# ProDocument__DCDC_2024-01-08.net
KiCad netlist of a schematic drawn in EasyEDA Pro
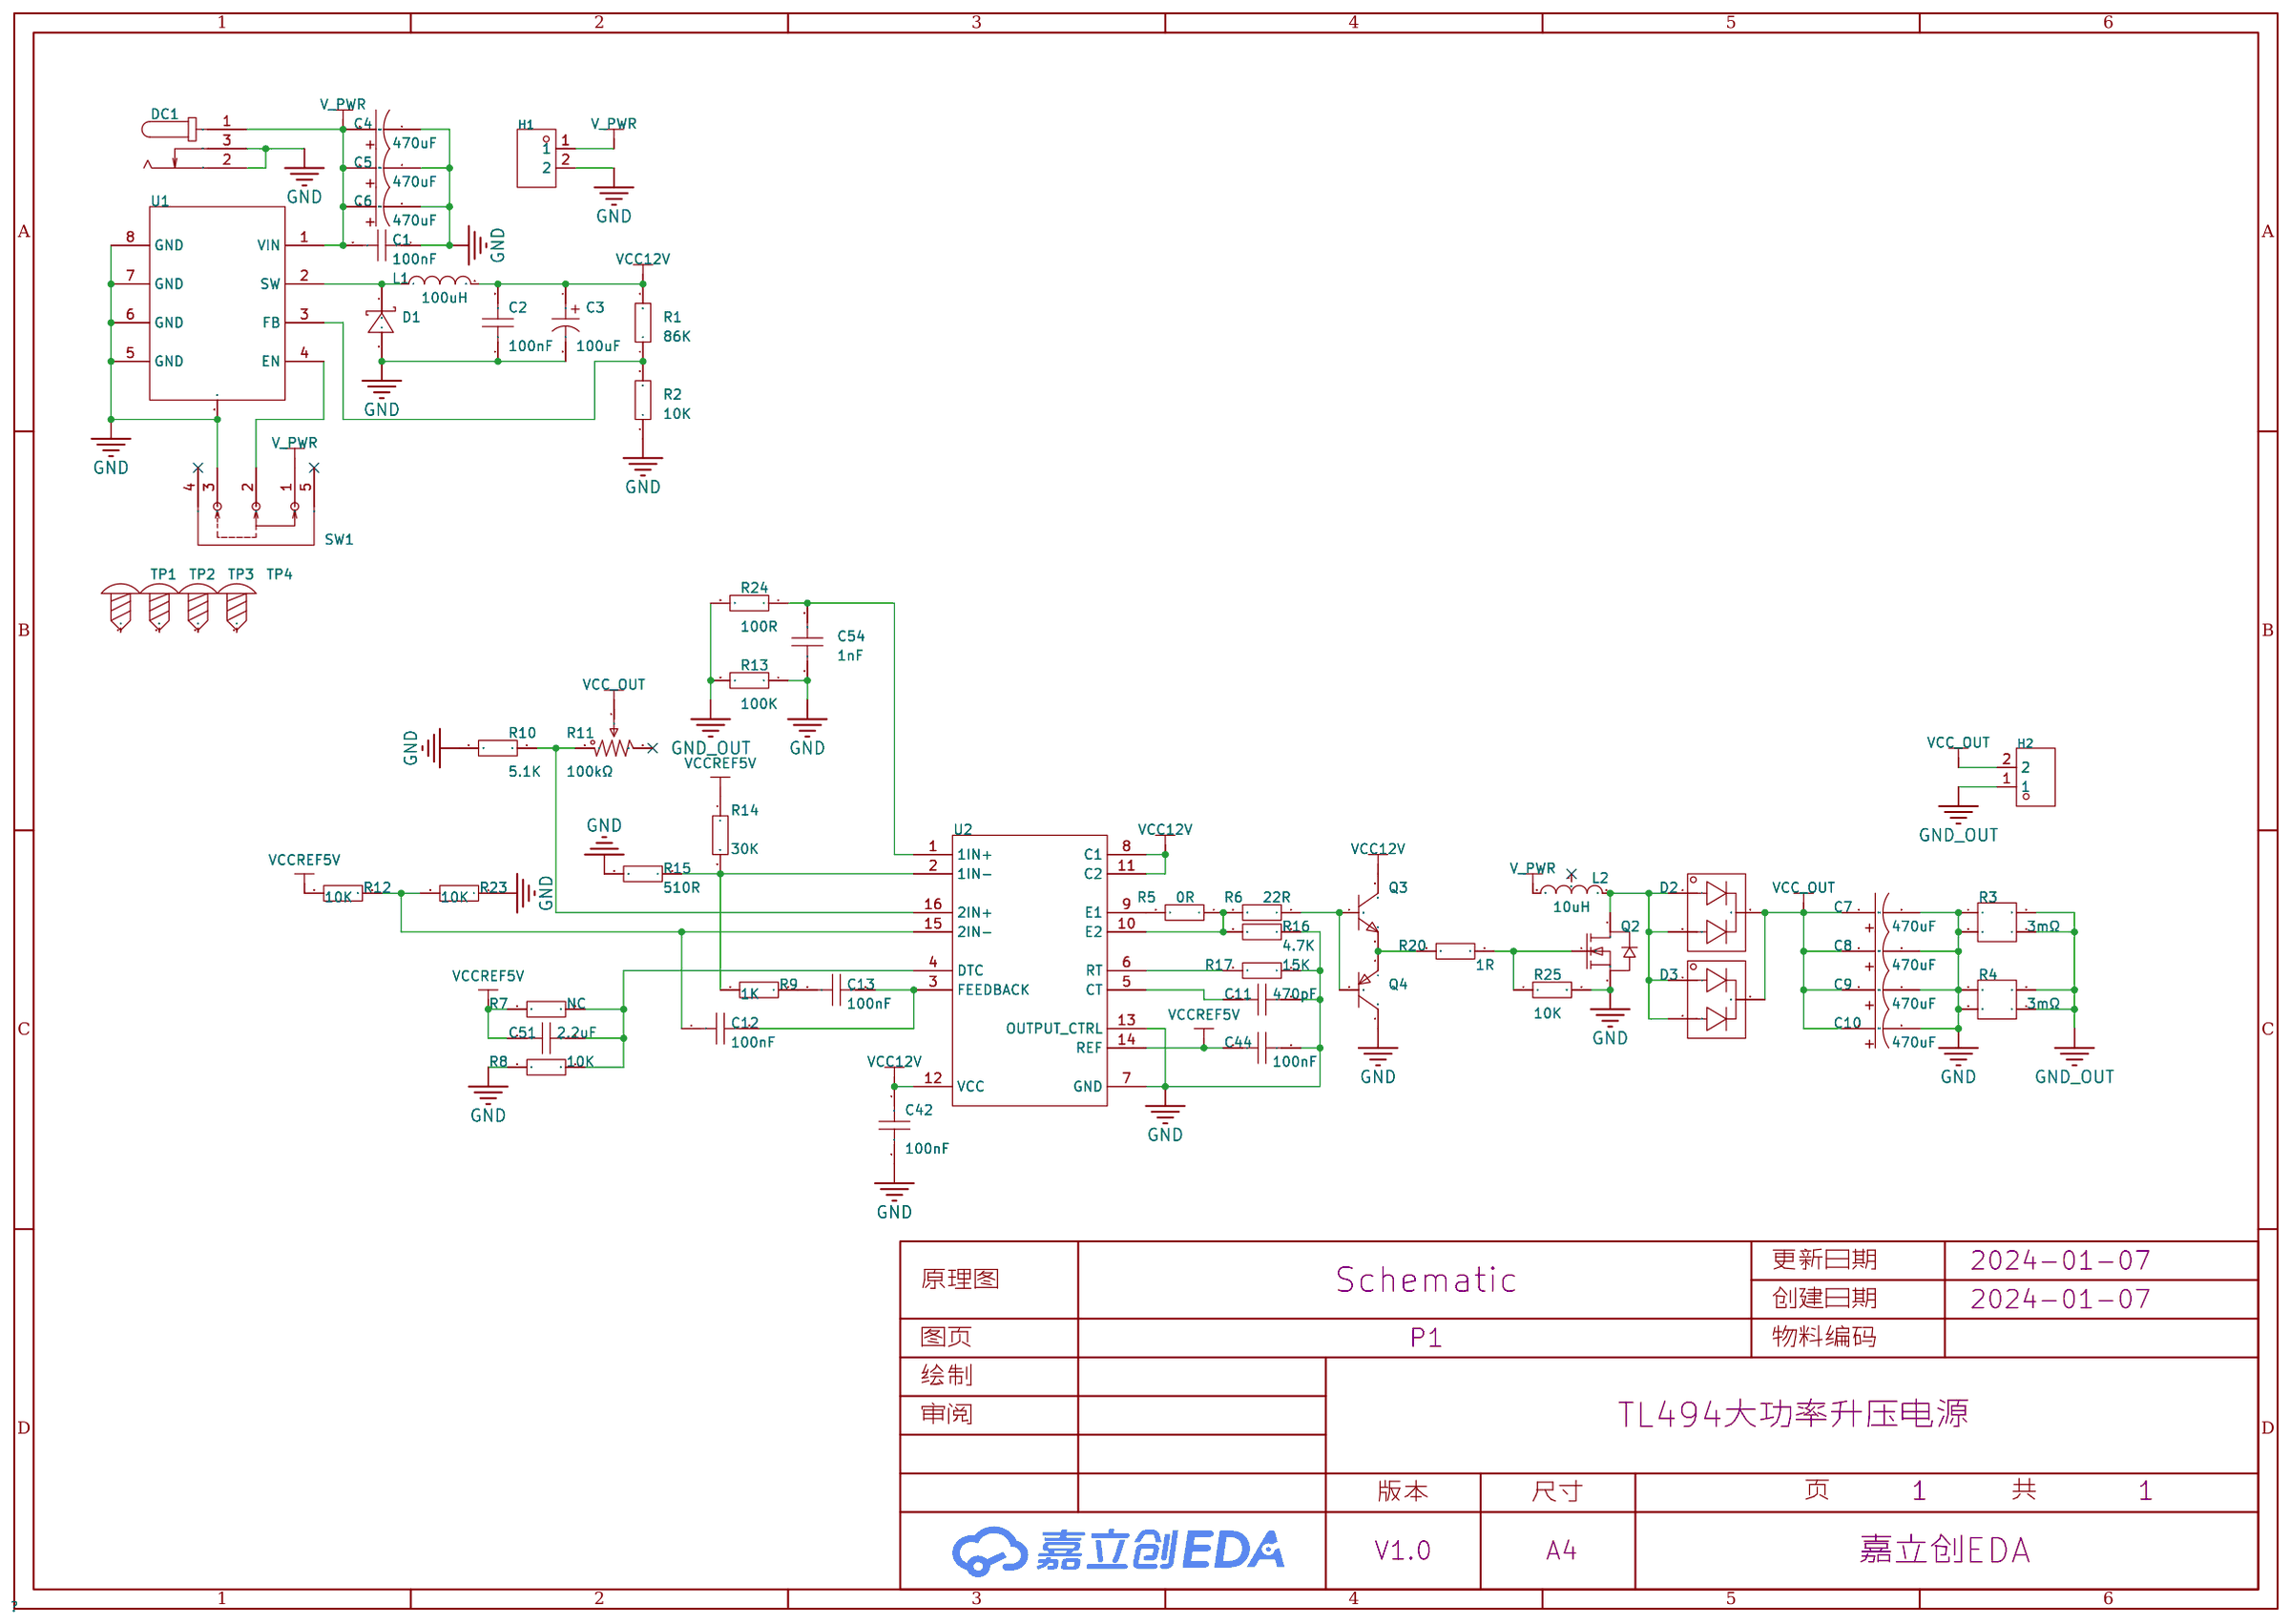
[diagram p0: schematic sheet]

(export (version "E")
  (design (tool "Eeschema 10.0.6"))
  (components
    (comp (ref "C1")
      (value "100nF")
      (footprint "easyedapro:C0603")
      (libsource (lib "easyedapro") (part "CapAcitance"))
    )
    (comp (ref "C2")
      (value "100nF")
      (footprint "easyedapro:C0603")
      (libsource (lib "easyedapro") (part "CapAcitance"))
    )
    (comp (ref "C3")
      (value "100uF")
      (footprint "easyedapro:CAP-SMD_BD6.3-L6.6-W6.6-LS7.6-FD-1")
      (description "容值:100uF;精度:±20%;额定电压:35V;纹波电流:230mA@120Hz;等效串联电阻:600mΩ@100kHz;")
      (fields
        (field (name "Manufacturer Part") "RVE100UF35V67RV0072")
        (field (name "Manufacturer") "KNSCHA(科尼盛)")
      )
      (libsource (lib "easyedapro") (part "RVE100UF35V67RV0072"))
    )
    (comp (ref "C4")
      (value "470uF")
      (footprint "easyedapro:CAP-TH_BD16.0-P7.50-D1.2-FD")
      (description "容值:470uF;精度:±20%;额定电压:100V;纹波电流:-;等效串联电阻:-;")
      (fields (field (name "Manufacturer Part") "ERE1KM471L25OT") (field (name "Manufacturer") "AISHI(艾华集团)"))
      (libsource (lib "easyedapro") (part "ERE1KM471L25OT"))
    )
    (comp (ref "C5")
      (value "470uF")
      (footprint "easyedapro:CAP-TH_BD16.0-P7.50-D1.2-FD")
      (description "容值:470uF;精度:±20%;额定电压:100V;纹波电流:-;等效串联电阻:-;")
      (fields (field (name "Manufacturer Part") "ERE1KM471L25OT") (field (name "Manufacturer") "AISHI(艾华集团)"))
      (libsource (lib "easyedapro") (part "ERE1KM471L25OT"))
    )
    (comp (ref "C6")
      (value "470uF")
      (footprint "easyedapro:CAP-TH_BD16.0-P7.50-D1.2-FD")
      (description "容值:470uF;精度:±20%;额定电压:100V;纹波电流:-;等效串联电阻:-;")
      (fields (field (name "Manufacturer Part") "ERE1KM471L25OT") (field (name "Manufacturer") "AISHI(艾华集团)"))
      (libsource (lib "easyedapro") (part "ERE1KM471L25OT"))
    )
    (comp (ref "C7")
      (value "470uF")
      (footprint "easyedapro:CAP-TH_BD16.0-P7.50-D1.2-FD")
      (description "容值:470uF;精度:±20%;额定电压:100V;纹波电流:-;等效串联电阻:-;")
      (fields (field (name "Manufacturer Part") "ERE1KM471L25OT") (field (name "Manufacturer") "AISHI(艾华集团)"))
      (libsource (lib "easyedapro") (part "ERE1KM471L25OT"))
    )
    (comp (ref "C8")
      (value "470uF")
      (footprint "easyedapro:CAP-TH_BD16.0-P7.50-D1.2-FD")
      (description "容值:470uF;精度:±20%;额定电压:100V;纹波电流:-;等效串联电阻:-;")
      (fields (field (name "Manufacturer Part") "ERE1KM471L25OT") (field (name "Manufacturer") "AISHI(艾华集团)"))
      (libsource (lib "easyedapro") (part "ERE1KM471L25OT"))
    )
    (comp (ref "C9")
      (value "470uF")
      (footprint "easyedapro:CAP-TH_BD16.0-P7.50-D1.2-FD")
      (description "容值:470uF;精度:±20%;额定电压:100V;纹波电流:-;等效串联电阻:-;")
      (fields (field (name "Manufacturer Part") "ERE1KM471L25OT") (field (name "Manufacturer") "AISHI(艾华集团)"))
      (libsource (lib "easyedapro") (part "ERE1KM471L25OT"))
    )
    (comp (ref "C10")
      (value "470uF")
      (footprint "easyedapro:CAP-TH_BD16.0-P7.50-D1.2-FD")
      (description "容值:470uF;精度:±20%;额定电压:100V;纹波电流:-;等效串联电阻:-;")
      (fields (field (name "Manufacturer Part") "ERE1KM471L25OT") (field (name "Manufacturer") "AISHI(艾华集团)"))
      (libsource (lib "easyedapro") (part "ERE1KM471L25OT"))
    )
    (comp (ref "C11")
      (value "470pF")
      (footprint "easyedapro:C0603")
      (libsource (lib "easyedapro") (part "CapAcitance"))
    )
    (comp (ref "C12")
      (value "100nF")
      (footprint "easyedapro:C0603")
      (libsource (lib "easyedapro") (part "CapAcitance"))
    )
    (comp (ref "C13")
      (value "100nF")
      (footprint "easyedapro:C0603")
      (libsource (lib "easyedapro") (part "CapAcitance"))
    )
    (comp (ref "C42")
      (value "100nF")
      (footprint "easyedapro:C0603")
      (libsource (lib "easyedapro") (part "CapAcitance"))
    )
    (comp (ref "C44")
      (value "100nF")
      (footprint "easyedapro:C0603")
      (libsource (lib "easyedapro") (part "CapAcitance"))
    )
    (comp (ref "C51")
      (value "2.2uF")
      (footprint "easyedapro:C0603")
      (libsource (lib "easyedapro") (part "CapAcitance"))
    )
    (comp (ref "C54")
      (value "1nF")
      (footprint "easyedapro:C0603")
      (libsource (lib "easyedapro") (part "CapAcitance"))
    )
    (comp (ref "D1")
      (value "SS210")
      (footprint "easyedapro:SMA_L4.3-W2.6-LS5.2-RD")
      (description "直流反向耐压(Vr):100V;平均整流电流(Io):2A;正向压降(Vf):850mV@2A;")
      (fields (field (name "Manufacturer") "MDD"))
      (libsource (lib "easyedapro") (part "SS210"))
    )
    (comp (ref "D2")
      (value "MBRF20200CT")
      (footprint "easyedapro:ITO-220AB-3_L10.2-W4.5-P2.60-L")
      (description "正向压降(Vf):950mV@10A;直流反向耐压(Vr):200V;平均整流电流(Io):20A;")
      (fields (field (name "Manufacturer") "MDD"))
      (libsource (lib "easyedapro") (part "MBRF20200CT_C173470"))
    )
    (comp (ref "D3")
      (value "MBRF20200CT")
      (footprint "easyedapro:ITO-220AB-3_L10.2-W4.5-P2.60-L")
      (description "正向压降(Vf):950mV@10A;直流反向耐压(Vr):200V;平均整流电流(Io):20A;")
      (fields (field (name "Manufacturer") "MDD"))
      (libsource (lib "easyedapro") (part "MBRF20200CT_C173470"))
    )
    (comp (ref "DC1")
      (value "DC-005-20A")
      (footprint "easyedapro:DC-IN-TH_DC-005-20A")
      (description "触点内径:2mm;触点外径:6.4mm;额定电流:500mA;额定电压:30V;")
      (fields (field (name "Manufacturer") "韩国韩荣"))
      (libsource (lib "easyedapro") (part "DC-005-20A_C136744"))
    )
    (comp (ref "H1")
      (value "DBT50G-9.5-2P")
      (footprint "easyedapro:CONN-TH_2P-P9.50_DBT50G-9.5-2P")
      (fields (field (name "Manufacturer") "DIBO(地博电气)"))
      (libsource (lib "easyedapro") (part "DBT50G-9.5-2P"))
    )
    (comp (ref "H2")
      (value "DBT50G-9.5-2P")
      (footprint "easyedapro:CONN-TH_2P-P9.50_DBT50G-9.5-2P")
      (fields (field (name "Manufacturer") "DIBO(地博电气)"))
      (libsource (lib "easyedapro") (part "DBT50G-9.5-2P"))
    )
    (comp (ref "L1")
      (value "100uH")
      (footprint "easyedapro:IND-SMD_L7.1-W6.6")
      (description "电感值:100uH;精度:±20%;额定电流:1.5A;饱和电流(Isat):2A;")
      (fields (field (name "Manufacturer Part") "SMMS0650-101M") (field (name "Manufacturer") "SXN(顺翔诺)"))
      (libsource (lib "easyedapro") (part "SMMS0650-101M"))
    )
    (comp (ref "L2")
      (value "10uH")
      (footprint "easyedapro:IND-SMD_3P-L27.9-W19.7-P10.43-LS27.9-BL-A")
      (description "电感值:10uH;精度:±20%;额定电流:30A;类型:-;饱和电流(Isat):32.1A;")
      (fields (field (name "Manufacturer Part") "FC-SE2918-100M-28A") (field (name "Manufacturer") "FC(方成)"))
      (libsource (lib "easyedapro") (part "FC-SE2918-100M-28A"))
    )
    (comp (ref "Q2")
      (value "NCEP01T18T")
      (footprint "easyedapro:PG-TO247-3_L15.9-W5.2-P5.44-L")
      (fields (field (name "Manufacturer") "NCE(无锡新洁能)"))
      (libsource (lib "easyedapro") (part "NCEP01T18T"))
    )
    (comp (ref "Q3")
      (value "D882 Y档160~320")
      (footprint "easyedapro:SOT-89-3_L4.5-W2.5-P1.50-LS4.2-BR")
      (description "晶体管类型:NPN;集射极击穿电压(Vceo):30V;集电极电流(Ic):3A;功率(Pd):500mW;")
      (fields (field (name "Manufacturer") "CJ(江苏长电/长晶)"))
      (libsource (lib "easyedapro") (part "D882_C9634"))
    )
    (comp (ref "Q4")
      (value "B772")
      (footprint "easyedapro:SOT-89-3_L4.5-W2.5-P1.50-LS4.0-BR-1")
      (description "晶体管类型:PNP;集射极击穿电压(Vceo):30V;集电极电流(Ic):3A;功率(Pd):500mW;")
      (fields (field (name "Manufacturer") "CJ(江苏长电/长晶)"))
      (libsource (lib "easyedapro") (part "B772(SOT-89)"))
    )
    (comp (ref "R1") (value "86K") (footprint "easyedapro:R0603") (libsource (lib "easyedapro") (part "电阻")))
    (comp (ref "R2") (value "10K") (footprint "easyedapro:R0603") (libsource (lib "easyedapro") (part "电阻")))
    (comp (ref "R3")
      (value "3mΩ")
      (footprint "easyedapro:RES-TH_4P-L8.3-W5.3-P3.10-BL")
      (description "阻值:3mΩ;精度:±1%;功率:5W;")
      (fields
        (field (name "Manufacturer Part") "HOBH3820-5W-3mR-1%")
        (field (name "Manufacturer") "Milliohm(毫欧)")
      )
      (libsource (lib "easyedapro") (part "HOBH3820-5W-3MR-1%"))
    )
    (comp (ref "R4")
      (value "3mΩ")
      (footprint "easyedapro:RES-TH_4P-L8.3-W5.3-P3.10-BL")
      (description "阻值:3mΩ;精度:±1%;功率:5W;")
      (fields
        (field (name "Manufacturer Part") "HOBH3820-5W-3mR-1%")
        (field (name "Manufacturer") "Milliohm(毫欧)")
      )
      (libsource (lib "easyedapro") (part "HOBH3820-5W-3MR-1%"))
    )
    (comp (ref "R5") (value "0R") (footprint "easyedapro:R0603") (libsource (lib "easyedapro") (part "电阻")))
    (comp (ref "R6") (value "22R") (footprint "easyedapro:R0603") (libsource (lib "easyedapro") (part "电阻")))
    (comp (ref "R7") (value "NC") (footprint "easyedapro:R0603") (libsource (lib "easyedapro") (part "电阻")))
    (comp (ref "R8") (value "10K") (footprint "easyedapro:R0603") (libsource (lib "easyedapro") (part "电阻")))
    (comp (ref "R9") (value "1K") (footprint "easyedapro:R0603") (libsource (lib "easyedapro") (part "电阻")))
    (comp (ref "R10")
      (value "5.1K")
      (footprint "easyedapro:R0603")
      (libsource (lib "easyedapro") (part "电阻"))
    )
    (comp (ref "R11")
      (value "100kΩ")
      (footprint "easyedapro:RES-ADJ-TH_3362P")
      (description "阻值:100kΩ;精度:±10%;")
      (fields (field (name "Manufacturer Part") "3362P-1-104") (field (name "Manufacturer") "BOCHEN(博晨)"))
      (libsource (lib "easyedapro") (part "3362P-1-104_C118966"))
    )
    (comp (ref "R12") (value "10K") (footprint "easyedapro:R0603") (libsource (lib "easyedapro") (part "电阻")))
    (comp (ref "R13")
      (value "100K")
      (footprint "easyedapro:R0603")
      (libsource (lib "easyedapro") (part "电阻"))
    )
    (comp (ref "R14") (value "30K") (footprint "easyedapro:R0603") (libsource (lib "easyedapro") (part "电阻")))
    (comp (ref "R15")
      (value "510R")
      (footprint "easyedapro:R0603")
      (libsource (lib "easyedapro") (part "电阻"))
    )
    (comp (ref "R16")
      (value "4.7K")
      (footprint "easyedapro:R0603")
      (libsource (lib "easyedapro") (part "电阻"))
    )
    (comp (ref "R17") (value "15K") (footprint "easyedapro:R0603") (libsource (lib "easyedapro") (part "电阻")))
    (comp (ref "R20") (value "1R") (footprint "easyedapro:R0603") (libsource (lib "easyedapro") (part "电阻")))
    (comp (ref "R23") (value "10K") (footprint "easyedapro:R0603") (libsource (lib "easyedapro") (part "电阻")))
    (comp (ref "R24")
      (value "100R")
      (footprint "easyedapro:R0603")
      (libsource (lib "easyedapro") (part "电阻"))
    )
    (comp (ref "R25") (value "10K") (footprint "easyedapro:R0603") (libsource (lib "easyedapro") (part "电阻")))
    (comp (ref "SW1")
      (value "SK12D07VG4")
      (footprint "easyedapro:SW-TH_SK12D07VG4")
      (description "电路结构:单刀双掷;安装方式:卧插;额定电流(DC):500mA;额定电压(DC):50V;额定电流(AC):-;额定电压(AC):-;机械寿命:5千次;")
      (fields (field (name "Manufacturer") "SHOU HAN(首韩)"))
      (libsource (lib "easyedapro") (part "SK12D07VG4"))
    )
    (comp (ref "TP1") (value "~") (footprint "easyedapro:M3螺丝") (libsource (lib "easyedapro") (part "螺丝孔")))
    (comp (ref "TP2") (value "~") (footprint "easyedapro:M3螺丝") (libsource (lib "easyedapro") (part "螺丝孔")))
    (comp (ref "TP3") (value "~") (footprint "easyedapro:M3螺丝") (libsource (lib "easyedapro") (part "螺丝孔")))
    (comp (ref "TP4") (value "~") (footprint "easyedapro:M3螺丝") (libsource (lib "easyedapro") (part "螺丝孔")))
    (comp (ref "U1")
      (value "XL7005A")
      (footprint "easyedapro:SOIC-8_L4.9-W3.9-P1.27-LS6.0-BL-EP3.1-1")
      (description "功能类型:降压型;同步整流:-;输出通道数:-;拓扑结构:-;输入电压:-;输出电流(最大值):-;开关频率:-;")
      (fields (field (name "Manufacturer") "XLSEMI(芯龙)"))
      (libsource (lib "easyedapro") (part "XL7005A"))
    )
    (comp (ref "U2")
      (value "TL494CDR")
      (footprint "easyedapro:SOIC-16_L9.9-W3.9-P1.27-LS6.0-BL")
      (description "TL494 脉冲宽度调制 (Pwm) 控制电路")
      (fields (field (name "Manufacturer") "TI(德州仪器)"))
      (libsource (lib "easyedapro") (part "TL494CDR"))
    )
  )
  (nets
    (net (code "1") (name "GND") (class "Default")
      (node (ref "C1") (pin "1") (pinfunction "1_1") (pintype "input"))
      (node (ref "C10") (pin "2") (pinfunction "2_2") (pintype "input"))
      (node (ref "C11") (pin "2") (pinfunction "2_2") (pintype "input"))
      (node (ref "C2") (pin "1") (pinfunction "1_1") (pintype "input"))
      (node (ref "C3") (pin "2") (pinfunction "2_2") (pintype "input"))
      (node (ref "C4") (pin "2") (pinfunction "2_2") (pintype "input"))
      (node (ref "C42") (pin "2") (pinfunction "2_2") (pintype "input"))
      (node (ref "C44") (pin "2") (pinfunction "2_2") (pintype "input"))
      (node (ref "C5") (pin "2") (pinfunction "2_2") (pintype "input"))
      (node (ref "C54") (pin "1") (pinfunction "1_1") (pintype "input"))
      (node (ref "C6") (pin "2") (pinfunction "2_2") (pintype "input"))
      (node (ref "C7") (pin "2") (pinfunction "2_2") (pintype "input"))
      (node (ref "C8") (pin "2") (pinfunction "2_2") (pintype "input"))
      (node (ref "C9") (pin "2") (pinfunction "2_2") (pintype "input"))
      (node (ref "D1") (pin "2") (pinfunction "A_2") (pintype "input"))
      (node (ref "DC1") (pin "2") (pinfunction "2_2") (pintype "input"))
      (node (ref "DC1") (pin "3") (pinfunction "3_3") (pintype "input"))
      (node (ref "H1") (pin "2") (pinfunction "2_2") (pintype "input"))
      (node (ref "Q2") (pin "3") (pinfunction "S_3") (pintype "input"))
      (node (ref "Q4") (pin "2") (pinfunction "C_2") (pintype "input"))
      (node (ref "R10") (pin "2") (pinfunction "2_2") (pintype "input"))
      (node (ref "R13") (pin "1") (pinfunction "1_1") (pintype "input"))
      (node (ref "R15") (pin "2") (pinfunction "2_2") (pintype "input"))
      (node (ref "R16") (pin "1") (pinfunction "1_1") (pintype "input"))
      (node (ref "R17") (pin "1") (pinfunction "1_1") (pintype "input"))
      (node (ref "R2") (pin "1") (pinfunction "1_1") (pintype "input"))
      (node (ref "R23") (pin "1") (pinfunction "1_1") (pintype "input"))
      (node (ref "R25") (pin "2") (pinfunction "2_2") (pintype "input"))
      (node (ref "R3") (pin "1") (pinfunction "1_1") (pintype "input"))
      (node (ref "R3") (pin "3") (pinfunction "3_3") (pintype "input"))
      (node (ref "R4") (pin "1") (pinfunction "1_1") (pintype "input"))
      (node (ref "R4") (pin "3") (pinfunction "3_3") (pintype "input"))
      (node (ref "R8") (pin "2") (pinfunction "2_2") (pintype "input"))
      (node (ref "SW1") (pin "3") (pinfunction "3_3") (pintype "unspecified"))
      (node (ref "U1") (pin "5") (pinfunction "GND_5") (pintype "input"))
      (node (ref "U1") (pin "6") (pinfunction "GND_6") (pintype "input"))
      (node (ref "U1") (pin "7") (pinfunction "GND_7") (pintype "input"))
      (node (ref "U1") (pin "8") (pinfunction "GND_8") (pintype "input"))
      (node (ref "U1") (pin "9") (pinfunction "9_9") (pintype "input"))
      (node (ref "U2") (pin "13") (pinfunction "OUTPUT_CTRL_13") (pintype "input"))
      (node (ref "U2") (pin "7") (pinfunction "GND_7") (pintype "input"))
    )
    (net (code "2") (name "GND_OUT") (class "Default")
      (node (ref "H2") (pin "1") (pinfunction "1_1") (pintype "input"))
      (node (ref "R13") (pin "2") (pinfunction "2_2") (pintype "input"))
      (node (ref "R24") (pin "2") (pinfunction "2_2") (pintype "input"))
      (node (ref "R3") (pin "2") (pinfunction "2_2") (pintype "input"))
      (node (ref "R3") (pin "4") (pinfunction "4_4") (pintype "input"))
      (node (ref "R4") (pin "2") (pinfunction "2_2") (pintype "input"))
      (node (ref "R4") (pin "4") (pinfunction "4_4") (pintype "input"))
    )
    (net (code "3") (name "Net-(C13-Pad1)") (class "Default")
      (node (ref "C13") (pin "1") (pinfunction "1_1") (pintype "input"))
      (node (ref "R9") (pin "1") (pinfunction "1_1") (pintype "input"))
    )
    (net (code "4") (name "Net-(D1-K)") (class "Default")
      (node (ref "D1") (pin "1") (pinfunction "K_1") (pintype "input"))
      (node (ref "L1") (pin "1") (pinfunction "1_1") (pintype "input"))
      (node (ref "U1") (pin "2") (pinfunction "SW_2") (pintype "input"))
    )
    (net (code "5") (name "Net-(Q2-D)") (class "Default")
      (node (ref "D2") (pin "1") (pinfunction "1_1") (pintype "unspecified"))
      (node (ref "D2") (pin "3") (pinfunction "3_3") (pintype "unspecified"))
      (node (ref "D3") (pin "1") (pinfunction "1_1") (pintype "unspecified"))
      (node (ref "D3") (pin "3") (pinfunction "3_3") (pintype "unspecified"))
      (node (ref "L2") (pin "1") (pinfunction "1_1") (pintype "unspecified"))
      (node (ref "Q2") (pin "2") (pinfunction "D_2") (pintype "input"))
    )
    (net (code "6") (name "Net-(Q2-G)") (class "Default")
      (node (ref "Q2") (pin "1") (pinfunction "G_1") (pintype "input"))
      (node (ref "R20") (pin "1") (pinfunction "1_1") (pintype "input"))
      (node (ref "R25") (pin "1") (pinfunction "1_1") (pintype "input"))
    )
    (net (code "7") (name "Net-(Q3-B)") (class "Default")
      (node (ref "Q3") (pin "1") (pinfunction "B_1") (pintype "input"))
      (node (ref "Q4") (pin "1") (pinfunction "B_1") (pintype "input"))
      (node (ref "R6") (pin "1") (pinfunction "1_1") (pintype "input"))
    )
    (net (code "8") (name "Net-(Q3-E)") (class "Default")
      (node (ref "Q3") (pin "3") (pinfunction "E_3") (pintype "input"))
      (node (ref "Q4") (pin "3") (pinfunction "E_3") (pintype "input"))
      (node (ref "R20") (pin "2") (pinfunction "2_2") (pintype "input"))
    )
    (net (code "9") (name "Net-(U1-EN)") (class "Default")
      (node (ref "SW1") (pin "2") (pinfunction "2_2") (pintype "unspecified"))
      (node (ref "U1") (pin "4") (pinfunction "EN_4") (pintype "input"))
    )
    (net (code "10") (name "Net-(U1-FB)") (class "Default")
      (node (ref "R1") (pin "1") (pinfunction "1_1") (pintype "input"))
      (node (ref "R2") (pin "2") (pinfunction "2_2") (pintype "input"))
      (node (ref "U1") (pin "3") (pinfunction "FB_3") (pintype "input"))
    )
    (net (code "11") (name "Net-(U2-1IN+)") (class "Default")
      (node (ref "C54") (pin "2") (pinfunction "2_2") (pintype "input"))
      (node (ref "R24") (pin "1") (pinfunction "1_1") (pintype "input"))
      (node (ref "U2") (pin "1") (pinfunction "1IN+_1") (pintype "input"))
    )
    (net (code "12") (name "Net-(U2-1IN-)") (class "Default")
      (node (ref "R14") (pin "2") (pinfunction "2_2") (pintype "input"))
      (node (ref "R15") (pin "1") (pinfunction "1_1") (pintype "input"))
      (node (ref "R9") (pin "2") (pinfunction "2_2") (pintype "input"))
      (node (ref "U2") (pin "2") (pinfunction "1IN-_2") (pintype "input"))
    )
    (net (code "13") (name "Net-(U2-2IN+)") (class "Default")
      (node (ref "R10") (pin "1") (pinfunction "1_1") (pintype "input"))
      (node (ref "R11") (pin "1") (pinfunction "1_1") (pintype "input"))
      (node (ref "U2") (pin "16") (pinfunction "2IN+_16") (pintype "input"))
    )
    (net (code "14") (name "Net-(U2-2IN-)") (class "Default")
      (node (ref "C12") (pin "1") (pinfunction "1_1") (pintype "input"))
      (node (ref "R12") (pin "1") (pinfunction "1_1") (pintype "input"))
      (node (ref "R23") (pin "2") (pinfunction "2_2") (pintype "input"))
      (node (ref "U2") (pin "15") (pinfunction "2IN-_15") (pintype "input"))
    )
    (net (code "15") (name "Net-(U2-CT)") (class "Default")
      (node (ref "C11") (pin "1") (pinfunction "1_1") (pintype "input"))
      (node (ref "U2") (pin "5") (pinfunction "CT_5") (pintype "input"))
    )
    (net (code "16") (name "Net-(U2-DTC)") (class "Default")
      (node (ref "C51") (pin "2") (pinfunction "2_2") (pintype "input"))
      (node (ref "R7") (pin "1") (pinfunction "1_1") (pintype "input"))
      (node (ref "R8") (pin "1") (pinfunction "1_1") (pintype "input"))
      (node (ref "U2") (pin "4") (pinfunction "DTC_4") (pintype "input"))
    )
    (net (code "17") (name "Net-(U2-E1)") (class "Default")
      (node (ref "R5") (pin "2") (pinfunction "2_2") (pintype "input"))
      (node (ref "U2") (pin "9") (pinfunction "E1_9") (pintype "input"))
    )
    (net (code "18") (name "Net-(U2-E2)") (class "Default")
      (node (ref "R16") (pin "2") (pinfunction "2_2") (pintype "input"))
      (node (ref "R5") (pin "1") (pinfunction "1_1") (pintype "input"))
      (node (ref "R6") (pin "2") (pinfunction "2_2") (pintype "input"))
      (node (ref "U2") (pin "10") (pinfunction "E2_10") (pintype "input"))
    )
    (net (code "19") (name "Net-(U2-FEEDBACK)") (class "Default")
      (node (ref "C12") (pin "2") (pinfunction "2_2") (pintype "input"))
      (node (ref "C13") (pin "2") (pinfunction "2_2") (pintype "input"))
      (node (ref "U2") (pin "3") (pinfunction "FEEDBACK_3") (pintype "input"))
    )
    (net (code "20") (name "Net-(U2-RT)") (class "Default")
      (node (ref "R17") (pin "2") (pinfunction "2_2") (pintype "input"))
      (node (ref "U2") (pin "6") (pinfunction "RT_6") (pintype "input"))
    )
    (net (code "21") (name "VCC12V") (class "Default")
      (node (ref "C2") (pin "2") (pinfunction "2_2") (pintype "input"))
      (node (ref "C3") (pin "1") (pinfunction "1_1") (pintype "input"))
      (node (ref "C42") (pin "1") (pinfunction "1_1") (pintype "input"))
      (node (ref "L1") (pin "2") (pinfunction "2_2") (pintype "input"))
      (node (ref "Q3") (pin "2") (pinfunction "C_2") (pintype "input"))
      (node (ref "R1") (pin "2") (pinfunction "2_2") (pintype "input"))
      (node (ref "U2") (pin "11") (pinfunction "C2_11") (pintype "input"))
      (node (ref "U2") (pin "12") (pinfunction "VCC_12") (pintype "input"))
      (node (ref "U2") (pin "8") (pinfunction "C1_8") (pintype "input"))
    )
    (net (code "22") (name "VCCREF5V") (class "Default")
      (node (ref "C44") (pin "1") (pinfunction "1_1") (pintype "input"))
      (node (ref "C51") (pin "1") (pinfunction "1_1") (pintype "input"))
      (node (ref "R12") (pin "2") (pinfunction "2_2") (pintype "input"))
      (node (ref "R14") (pin "1") (pinfunction "1_1") (pintype "input"))
      (node (ref "R7") (pin "2") (pinfunction "2_2") (pintype "input"))
      (node (ref "U2") (pin "14") (pinfunction "REF_14") (pintype "output"))
    )
    (net (code "23") (name "VCC_OUT") (class "Default")
      (node (ref "C10") (pin "1") (pinfunction "1_1") (pintype "input"))
      (node (ref "C7") (pin "1") (pinfunction "1_1") (pintype "input"))
      (node (ref "C8") (pin "1") (pinfunction "1_1") (pintype "input"))
      (node (ref "C9") (pin "1") (pinfunction "1_1") (pintype "input"))
      (node (ref "D2") (pin "2") (pinfunction "2_2") (pintype "unspecified"))
      (node (ref "D3") (pin "2") (pinfunction "2_2") (pintype "unspecified"))
      (node (ref "H2") (pin "2") (pinfunction "2_2") (pintype "input"))
      (node (ref "R11") (pin "2") (pinfunction "2_2") (pintype "input"))
    )
    (net (code "24") (name "V_PWR") (class "Default")
      (node (ref "C1") (pin "2") (pinfunction "2_2") (pintype "input"))
      (node (ref "C4") (pin "1") (pinfunction "1_1") (pintype "input"))
      (node (ref "C5") (pin "1") (pinfunction "1_1") (pintype "input"))
      (node (ref "C6") (pin "1") (pinfunction "1_1") (pintype "input"))
      (node (ref "DC1") (pin "1") (pinfunction "1_1") (pintype "input"))
      (node (ref "H1") (pin "1") (pinfunction "1_1") (pintype "input"))
      (node (ref "L2") (pin "2") (pinfunction "2_2") (pintype "unspecified"))
      (node (ref "SW1") (pin "1") (pinfunction "1_1") (pintype "unspecified"))
      (node (ref "U1") (pin "1") (pinfunction "VIN_1") (pintype "input"))
    )
    (net (code "25") (name "unconnected-(L2-Pad3)") (class "Default")
      (node (ref "L2") (pin "3") (pinfunction "3_3") (pintype "unspecified+no_connect"))
    )
    (net (code "26") (name "unconnected-(R11-Pad3)") (class "Default")
      (node (ref "R11") (pin "3") (pinfunction "3_3") (pintype "input+no_connect"))
    )
    (net (code "27") (name "unconnected-(SW1-Pad4)") (class "Default")
      (node (ref "SW1") (pin "4") (pinfunction "4_4") (pintype "unspecified+no_connect"))
    )
    (net (code "28") (name "unconnected-(SW1-Pad5)") (class "Default")
      (node (ref "SW1") (pin "5") (pinfunction "5_5") (pintype "unspecified+no_connect"))
    )
    (net (code "29") (name "unconnected-(TP1-Pad1)") (class "Default")
      (node (ref "TP1") (pin "1") (pinfunction "1_1") (pintype "input"))
    )
    (net (code "30") (name "unconnected-(TP2-Pad1)") (class "Default")
      (node (ref "TP2") (pin "1") (pinfunction "1_1") (pintype "input"))
    )
    (net (code "31") (name "unconnected-(TP3-Pad1)") (class "Default")
      (node (ref "TP3") (pin "1") (pinfunction "1_1") (pintype "input"))
    )
    (net (code "32") (name "unconnected-(TP4-Pad1)") (class "Default")
      (node (ref "TP4") (pin "1") (pinfunction "1_1") (pintype "input"))
    )
  )
)
